# H00R2.net
KiCad netlist of a schematic drawn in EAGLE
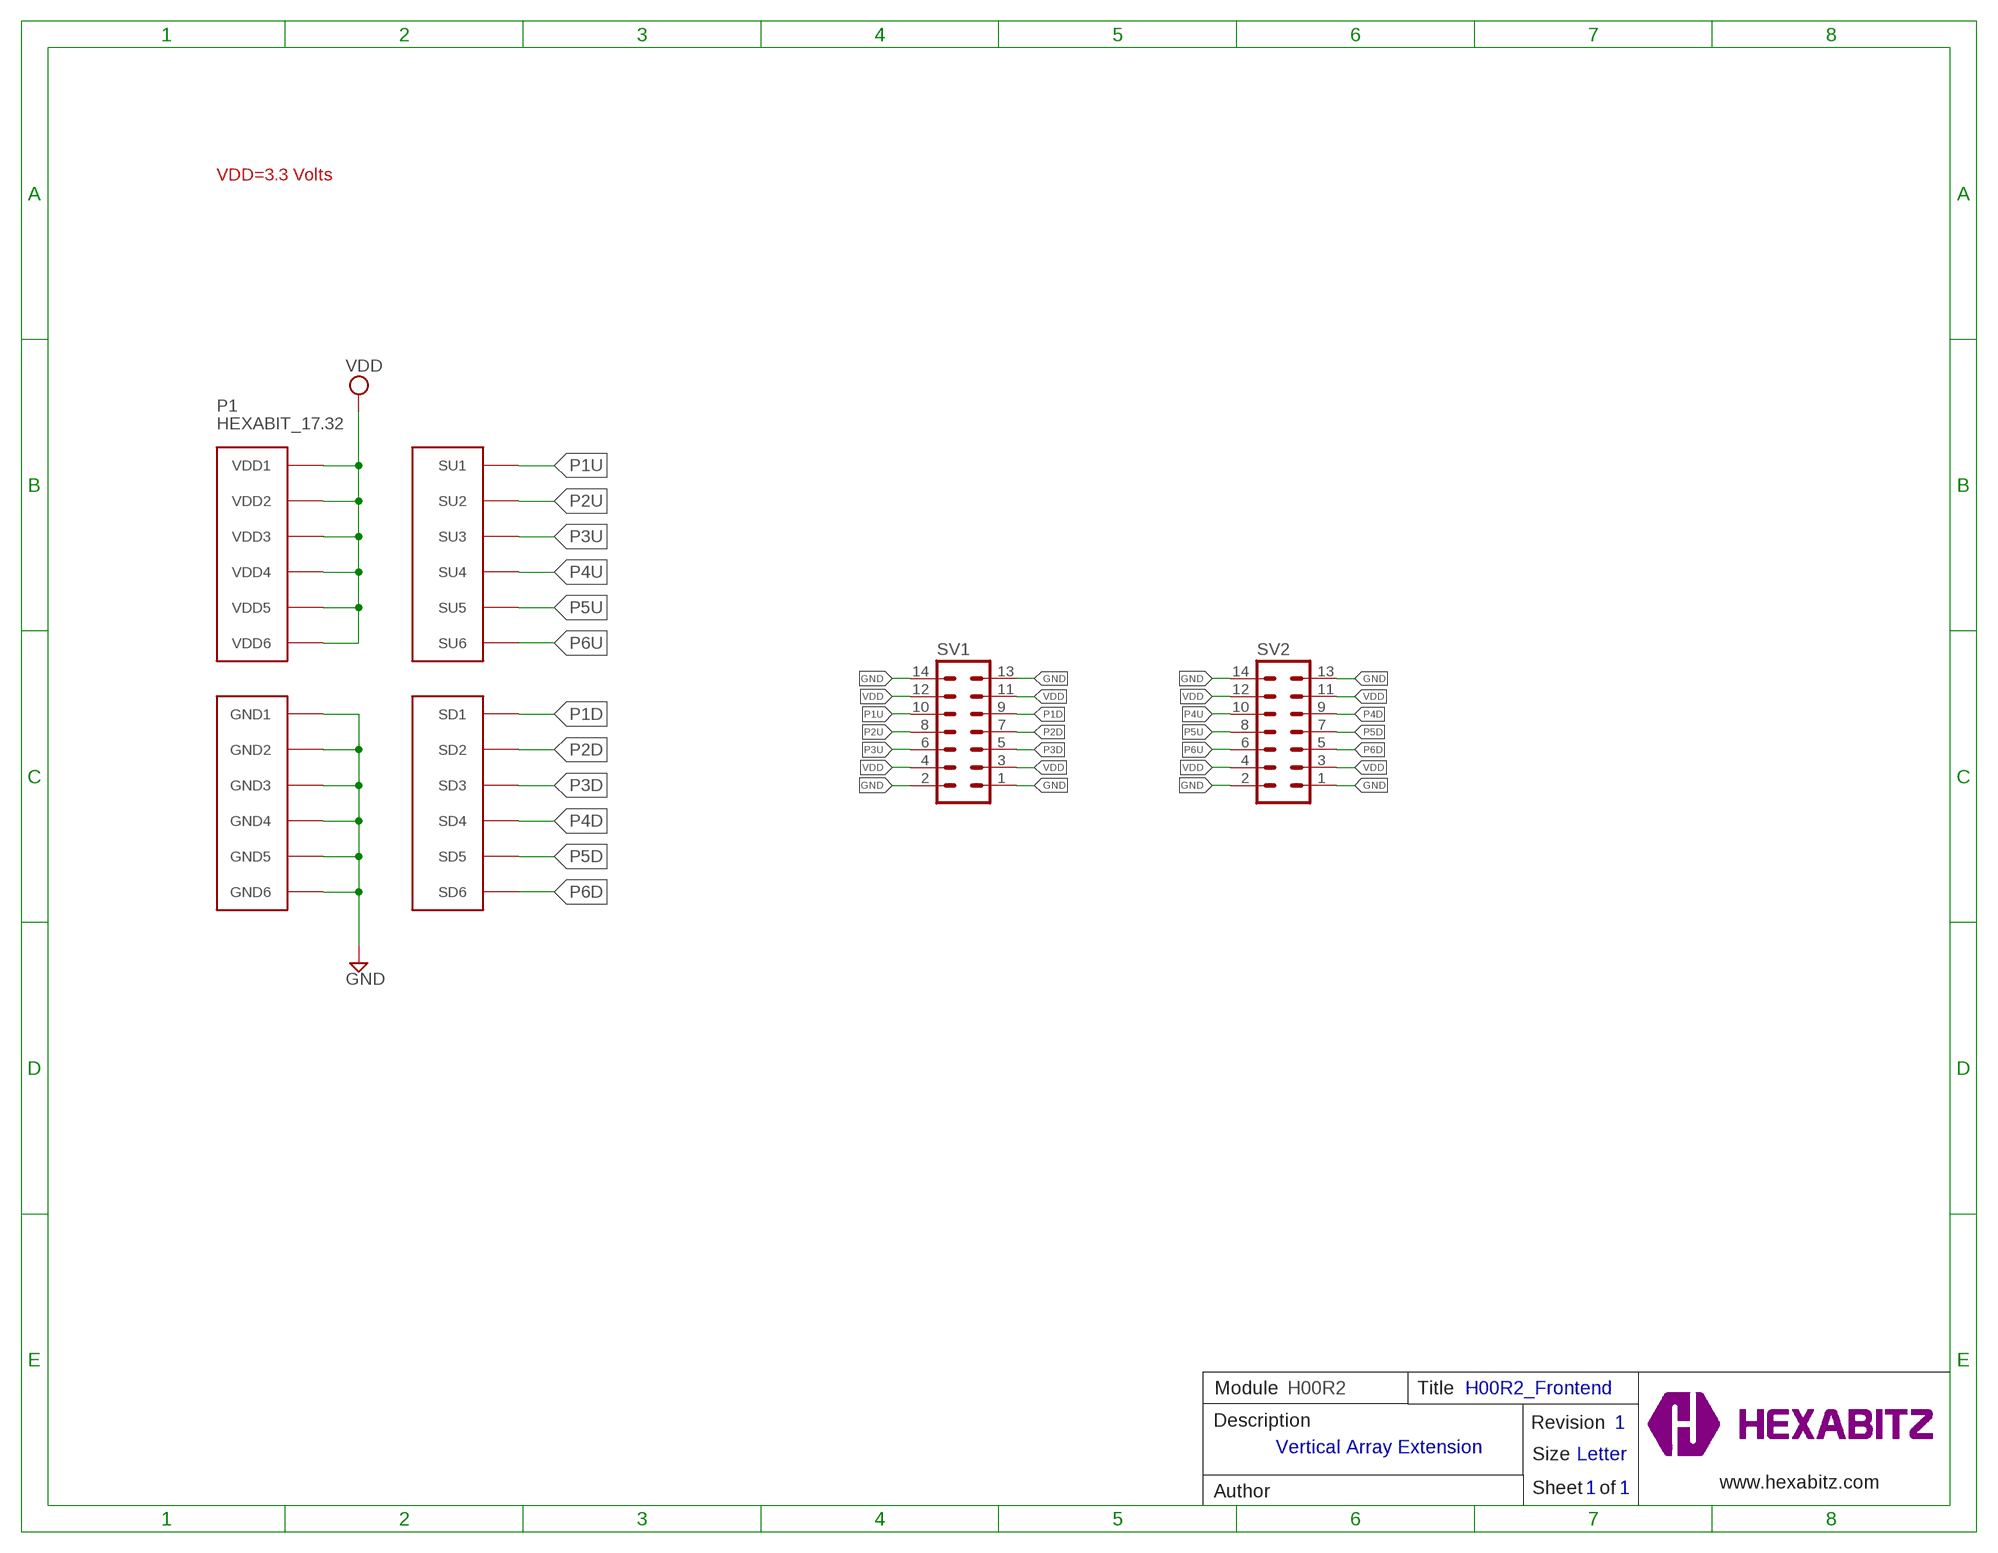
[diagram p0: schematic, sheet 1]

(export (version "E")
  (design (tool "Eeschema 10.0.6"))
  (components
    (comp (ref "P1")
      (value "HEXABIT_17.32")
      (footprint "eagle-import:HEXABIT_17.32")
      (libsource (lib "eagle-import") (part "HEXABIT_?17.32"))
    )
    (comp (ref "SV1")
      (value "MA07-2")
      (footprint "eagle-import:MA07-2")
      (libsource (lib "eagle-import") (part "MA07-2"))
    )
    (comp (ref "SV2")
      (value "MA07-2")
      (footprint "eagle-import:MA07-2")
      (libsource (lib "eagle-import") (part "MA07-2"))
    )
    (comp (ref "TRIMBLE-LOGO1")
      (value "HEXA-LOGO")
      (footprint "eagle-import:HEXA-LOGO")
      (libsource (lib "eagle-import") (part "HEXA-LOGO"))
    )
  )
  (nets
    (net (code "1") (name "GND") (class "Default")
      (node (ref "P1") (pin "PAD_PD10") (pinfunction "GND4_PAD_PD10") (pintype "power_in"))
      (node (ref "P1") (pin "PAD_PD11") (pinfunction "GND5_PAD_PD11") (pintype "power_in"))
      (node (ref "P1") (pin "PAD_PD12") (pinfunction "GND6_PAD_PD12") (pintype "power_in"))
      (node (ref "P1") (pin "PAD_PD7") (pinfunction "GND1_PAD_PD7") (pintype "power_in"))
      (node (ref "P1") (pin "PAD_PD8") (pinfunction "GND2_PAD_PD8") (pintype "power_in"))
      (node (ref "P1") (pin "PAD_PD9") (pinfunction "GND3_PAD_PD9") (pintype "power_in"))
      (node (ref "SV1") (pin "1") (pinfunction "1_1") (pintype "passive"))
      (node (ref "SV1") (pin "13") (pinfunction "13_13") (pintype "passive"))
      (node (ref "SV1") (pin "14") (pinfunction "14_14") (pintype "passive"))
      (node (ref "SV1") (pin "2") (pinfunction "2_2") (pintype "passive"))
      (node (ref "SV2") (pin "1") (pinfunction "1_1") (pintype "passive"))
      (node (ref "SV2") (pin "13") (pinfunction "13_13") (pintype "passive"))
      (node (ref "SV2") (pin "14") (pinfunction "14_14") (pintype "passive"))
      (node (ref "SV2") (pin "2") (pinfunction "2_2") (pintype "passive"))
    )
    (net (code "2") (name "P1D") (class "Default")
      (node (ref "P1") (pin "PAD_PD1") (pinfunction "SD1_PAD_PD1") (pintype "bidirectional"))
      (node (ref "SV1") (pin "9") (pinfunction "9_9") (pintype "passive"))
    )
    (net (code "3") (name "P1U") (class "Default")
      (node (ref "P1") (pin "PAD_PU1") (pinfunction "SU1_PAD_PU1") (pintype "bidirectional"))
      (node (ref "SV1") (pin "10") (pinfunction "10_10") (pintype "passive"))
    )
    (net (code "4") (name "P2D") (class "Default")
      (node (ref "P1") (pin "PAD_PD2") (pinfunction "SD2_PAD_PD2") (pintype "bidirectional"))
      (node (ref "SV1") (pin "7") (pinfunction "7_7") (pintype "passive"))
    )
    (net (code "5") (name "P2U") (class "Default")
      (node (ref "P1") (pin "PAD_PU2") (pinfunction "SU2_PAD_PU2") (pintype "bidirectional"))
      (node (ref "SV1") (pin "8") (pinfunction "8_8") (pintype "passive"))
    )
    (net (code "6") (name "P3D") (class "Default")
      (node (ref "P1") (pin "PAD_PD3") (pinfunction "SD3_PAD_PD3") (pintype "bidirectional"))
      (node (ref "SV1") (pin "5") (pinfunction "5_5") (pintype "passive"))
    )
    (net (code "7") (name "P3U") (class "Default")
      (node (ref "P1") (pin "PAD_PU3") (pinfunction "SU3_PAD_PU3") (pintype "bidirectional"))
      (node (ref "SV1") (pin "6") (pinfunction "6_6") (pintype "passive"))
    )
    (net (code "8") (name "P4D") (class "Default")
      (node (ref "P1") (pin "PAD_PD4") (pinfunction "SD4_PAD_PD4") (pintype "bidirectional"))
      (node (ref "SV2") (pin "9") (pinfunction "9_9") (pintype "passive"))
    )
    (net (code "9") (name "P4U") (class "Default")
      (node (ref "P1") (pin "PAD_PU4") (pinfunction "SU4_PAD_PU4") (pintype "bidirectional"))
      (node (ref "SV2") (pin "10") (pinfunction "10_10") (pintype "passive"))
    )
    (net (code "10") (name "P5D") (class "Default")
      (node (ref "P1") (pin "PAD_PD5") (pinfunction "SD5_PAD_PD5") (pintype "bidirectional"))
      (node (ref "SV2") (pin "7") (pinfunction "7_7") (pintype "passive"))
    )
    (net (code "11") (name "P5U") (class "Default")
      (node (ref "P1") (pin "PAD_PU5") (pinfunction "SU5_PAD_PU5") (pintype "bidirectional"))
      (node (ref "SV2") (pin "8") (pinfunction "8_8") (pintype "passive"))
    )
    (net (code "12") (name "P6D") (class "Default")
      (node (ref "P1") (pin "PAD_PD6") (pinfunction "SD6_PAD_PD6") (pintype "bidirectional"))
      (node (ref "SV2") (pin "5") (pinfunction "5_5") (pintype "passive"))
    )
    (net (code "13") (name "P6U") (class "Default")
      (node (ref "P1") (pin "PAD_PU6") (pinfunction "SU6_PAD_PU6") (pintype "bidirectional"))
      (node (ref "SV2") (pin "6") (pinfunction "6_6") (pintype "passive"))
    )
    (net (code "14") (name "VDD") (class "Default")
      (node (ref "P1") (pin "PAD_PU10") (pinfunction "VDD4_PAD_PU10") (pintype "power_in"))
      (node (ref "P1") (pin "PAD_PU11") (pinfunction "VDD5_PAD_PU11") (pintype "power_in"))
      (node (ref "P1") (pin "PAD_PU12") (pinfunction "VDD6_PAD_PU12") (pintype "power_in"))
      (node (ref "P1") (pin "PAD_PU7") (pinfunction "VDD1_PAD_PU7") (pintype "power_in"))
      (node (ref "P1") (pin "PAD_PU8") (pinfunction "VDD2_PAD_PU8") (pintype "power_in"))
      (node (ref "P1") (pin "PAD_PU9") (pinfunction "VDD3_PAD_PU9") (pintype "power_in"))
      (node (ref "SV1") (pin "11") (pinfunction "11_11") (pintype "passive"))
      (node (ref "SV1") (pin "12") (pinfunction "12_12") (pintype "passive"))
      (node (ref "SV1") (pin "3") (pinfunction "3_3") (pintype "passive"))
      (node (ref "SV1") (pin "4") (pinfunction "4_4") (pintype "passive"))
      (node (ref "SV2") (pin "11") (pinfunction "11_11") (pintype "passive"))
      (node (ref "SV2") (pin "12") (pinfunction "12_12") (pintype "passive"))
      (node (ref "SV2") (pin "3") (pinfunction "3_3") (pintype "passive"))
      (node (ref "SV2") (pin "4") (pinfunction "4_4") (pintype "passive"))
    )
  )
)
